# USBasp_SMD.net
KiCad netlist of a schematic drawn in EAGLE
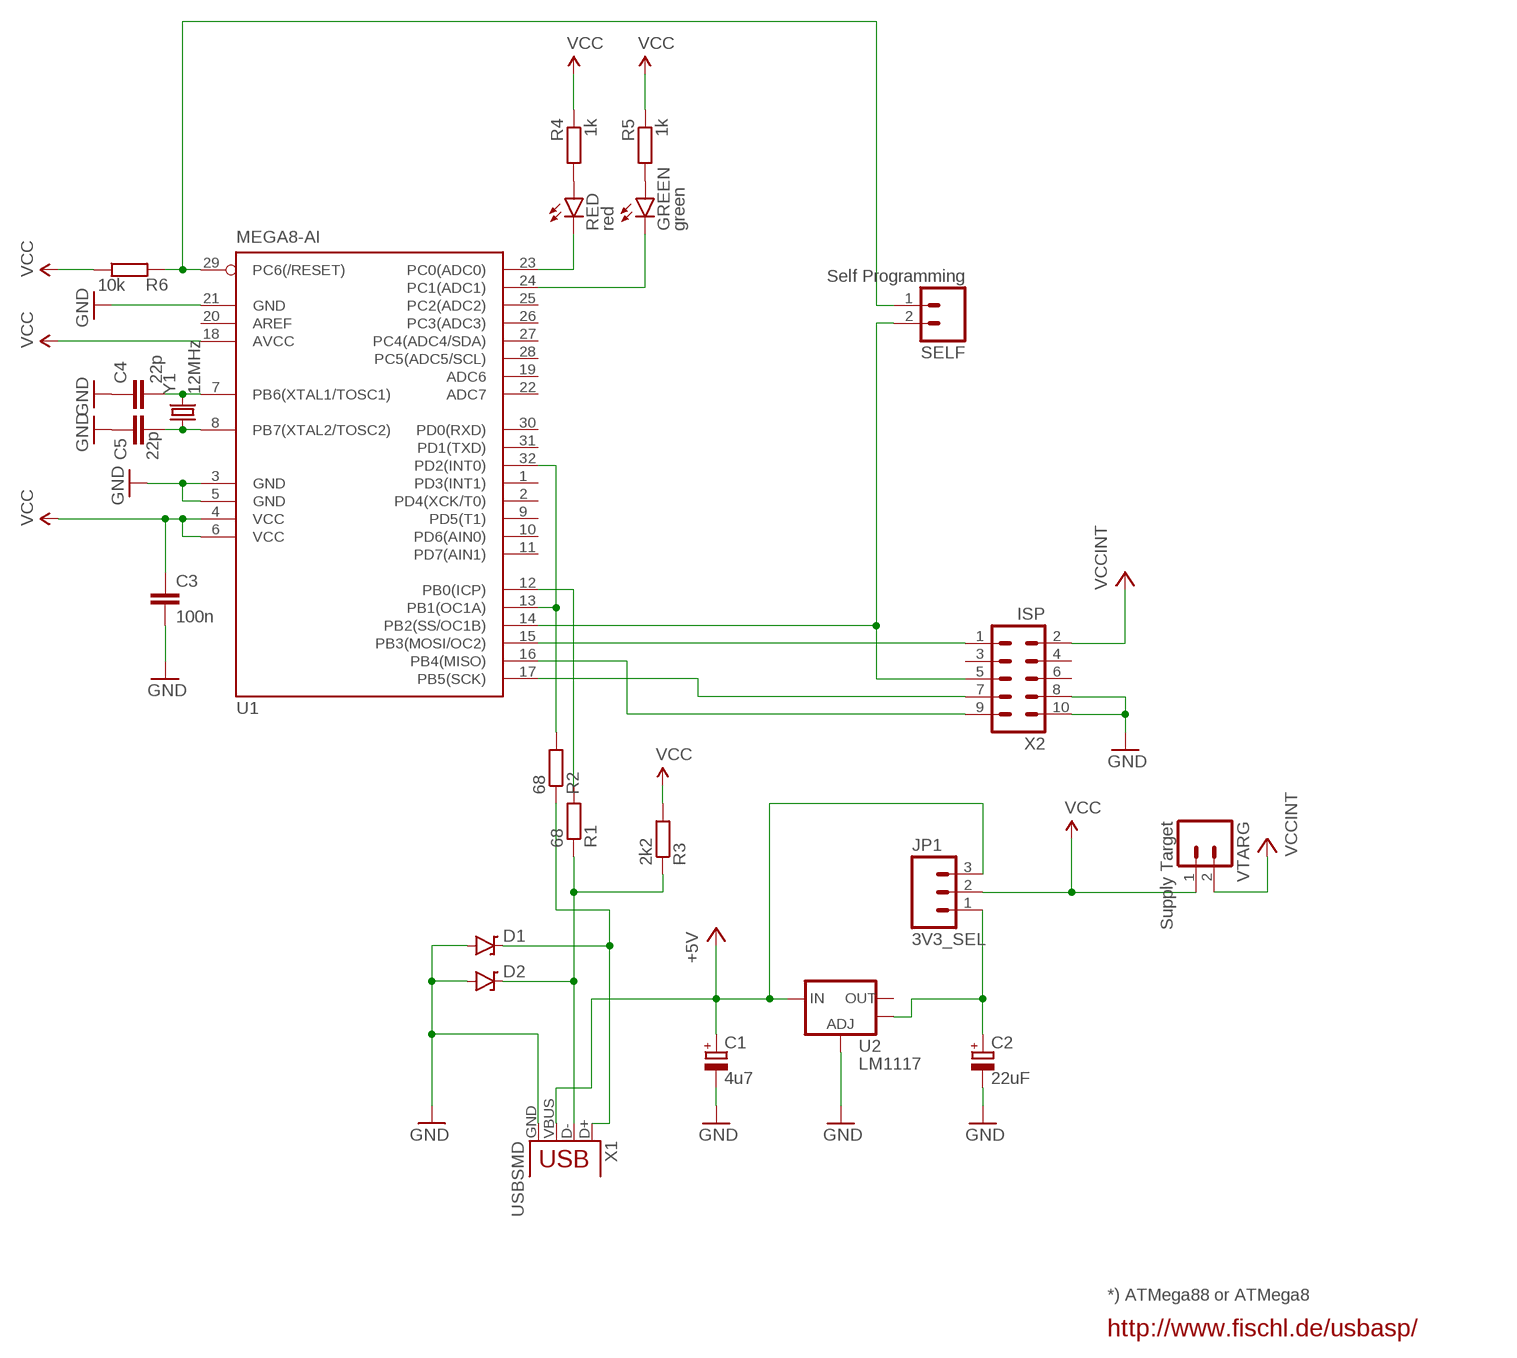
[diagram p0: schematic, sheet 1]

(export (version "E")
  (design (tool "Eeschema 10.0.6"))
  (components
    (comp (ref "C1")
      (value "4u7")
      (footprint "eagle-import:E2,5-5")
      (libsource (lib "eagle-import") (part "CPOL-EUE2.5-5"))
    )
    (comp (ref "C2")
      (value "22uF")
      (footprint "eagle-import:E2,5-5")
      (libsource (lib "eagle-import") (part "CPOL-EUE2.5-5"))
    )
    (comp (ref "C3")
      (value "100n")
      (footprint "eagle-import:C1206")
      (libsource (lib "eagle-import") (part "C-EUC1206"))
    )
    (comp (ref "C4")
      (value "22p")
      (footprint "eagle-import:C1206")
      (libsource (lib "eagle-import") (part "C-EUC1206"))
    )
    (comp (ref "C5")
      (value "22p")
      (footprint "eagle-import:C1206")
      (libsource (lib "eagle-import") (part "C-EUC1206"))
    )
    (comp (ref "D1")
      (value "3V6")
      (footprint "eagle-import:DIODE-ZENER")
      (libsource (lib "eagle-import") (part "DIODE-ZENERPTH"))
    )
    (comp (ref "D2")
      (value "3V6")
      (footprint "eagle-import:DIODE-ZENER")
      (libsource (lib "eagle-import") (part "DIODE-ZENERPTH"))
    )
    (comp (ref "GREEN")
      (value "green")
      (footprint "eagle-import:LED-1206")
      (libsource (lib "eagle-import") (part "LED1206"))
    )
    (comp (ref "JP1")
      (value "3V3_SEL")
      (footprint "eagle-import:1X03")
      (libsource (lib "eagle-import") (part "M03PTH"))
    )
    (comp (ref "R1")
      (value "68")
      (footprint "eagle-import:M1206")
      (libsource (lib "eagle-import") (part "R-EU_M1206"))
    )
    (comp (ref "R2")
      (value "68")
      (footprint "eagle-import:M1206")
      (libsource (lib "eagle-import") (part "R-EU_M1206"))
    )
    (comp (ref "R3")
      (value "2k2")
      (footprint "eagle-import:M1206")
      (libsource (lib "eagle-import") (part "R-EU_M1206"))
    )
    (comp (ref "R4")
      (value "1k")
      (footprint "eagle-import:M1206")
      (libsource (lib "eagle-import") (part "R-EU_M1206"))
    )
    (comp (ref "R5")
      (value "1k")
      (footprint "eagle-import:M1206")
      (libsource (lib "eagle-import") (part "R-EU_M1206"))
    )
    (comp (ref "R6")
      (value "10k")
      (footprint "eagle-import:M1206")
      (libsource (lib "eagle-import") (part "R-EU_M1206"))
    )
    (comp (ref "RED")
      (value "red")
      (footprint "eagle-import:LED-1206")
      (libsource (lib "eagle-import") (part "LED1206"))
    )
    (comp (ref "SELF")
      (value "Self Programming")
      (footprint "eagle-import:1X02")
      (libsource (lib "eagle-import") (part "M02PTH"))
    )
    (comp (ref "U1")
      (value "MEGA8-AI")
      (footprint "eagle-import:TQFP32-08")
      (fields (field (name "MPN") "ATMEGA8-16AU"))
      (libsource (lib "eagle-import") (part "MEGA8-AI"))
    )
    (comp (ref "U2")
      (value "LM1117")
      (footprint "eagle-import:SOT223")
      (libsource (lib "eagle-import") (part "V_REG_LM1117SOT223"))
    )
    (comp (ref "VTARG")
      (value "Supply Target")
      (footprint "eagle-import:1X02")
      (libsource (lib "eagle-import") (part "M02PTH"))
    )
    (comp (ref "X1")
      (value "USBSMD")
      (footprint "eagle-import:USB-MINIB")
      (libsource (lib "eagle-import") (part "USBSMD"))
    )
    (comp (ref "X2")
      (value "ISP")
      (footprint "eagle-import:ML10L")
      (libsource (lib "eagle-import") (part "ML10L"))
    )
    (comp (ref "Y1")
      (value "12MHz")
      (footprint "eagle-import:HC49UP")
      (libsource (lib "eagle-import") (part "CRYSTALSMD"))
    )
  )
  (nets
    (net (code "1") (name "+5V") (class "Default")
      (node (ref "C1") (pin "+") (pinfunction "+_+") (pintype "passive"))
      (node (ref "JP1") (pin "3") (pinfunction "3_3") (pintype "passive"))
      (node (ref "U2") (pin "3") (pinfunction "IN_3") (pintype "input"))
      (node (ref "X1") (pin "VBUS") (pinfunction "VBUS_VBUS") (pintype "bidirectional"))
    )
    (net (code "2") (name "GND") (class "Default")
      (node (ref "C1") (pin "-") (pinfunction "-_-") (pintype "passive"))
      (node (ref "C2") (pin "-") (pinfunction "-_-") (pintype "passive"))
      (node (ref "C3") (pin "2") (pinfunction "2_2") (pintype "passive"))
      (node (ref "C4") (pin "1") (pinfunction "1_1") (pintype "passive"))
      (node (ref "C5") (pin "1") (pinfunction "1_1") (pintype "passive"))
      (node (ref "D1") (pin "P$2") (pinfunction "A_P$2") (pintype "passive"))
      (node (ref "D2") (pin "P$2") (pinfunction "A_P$2") (pintype "passive"))
      (node (ref "U1") (pin "21") (pinfunction "GND_21") (pintype "power_in"))
      (node (ref "U1") (pin "3") (pinfunction "GND_3") (pintype "power_in"))
      (node (ref "U1") (pin "5") (pinfunction "GND_5") (pintype "power_in"))
      (node (ref "U2") (pin "1") (pinfunction "ADJ_1") (pintype "input"))
      (node (ref "X1") (pin "GND") (pinfunction "GND_GND") (pintype "bidirectional"))
      (node (ref "X2") (pin "10") (pinfunction "10_10") (pintype "passive"))
      (node (ref "X2") (pin "8") (pinfunction "8_8") (pintype "passive"))
    )
    (net (code "3") (name "Net-(C2-Pad+)") (class "Default")
      (node (ref "C2") (pin "+") (pinfunction "+_+") (pintype "passive"))
      (node (ref "JP1") (pin "1") (pinfunction "1_1") (pintype "passive"))
      (node (ref "U2") (pin "4") (pinfunction "OUT_4") (pintype "output"))
    )
    (net (code "4") (name "Net-(D1-C)") (class "Default")
      (node (ref "D1") (pin "P$1") (pinfunction "C_P$1") (pintype "passive"))
      (node (ref "R2") (pin "1") (pinfunction "1_1") (pintype "passive"))
      (node (ref "X1") (pin "D+") (pinfunction "D+_D+") (pintype "bidirectional"))
    )
    (net (code "5") (name "Net-(D2-C)") (class "Default")
      (node (ref "D2") (pin "P$1") (pinfunction "C_P$1") (pintype "passive"))
      (node (ref "R1") (pin "1") (pinfunction "1_1") (pintype "passive"))
      (node (ref "R3") (pin "1") (pinfunction "1_1") (pintype "passive"))
      (node (ref "X1") (pin "D-") (pinfunction "D-_D-") (pintype "bidirectional"))
    )
    (net (code "6") (name "Net-(GREEN-PadA)") (class "Default")
      (node (ref "GREEN") (pin "A") (pinfunction "A_A") (pintype "passive"))
      (node (ref "R5") (pin "2") (pinfunction "2_2") (pintype "passive"))
    )
    (net (code "7") (name "Net-(R4-Pad2)") (class "Default")
      (node (ref "R4") (pin "2") (pinfunction "2_2") (pintype "passive"))
      (node (ref "RED") (pin "A") (pinfunction "A_A") (pintype "passive"))
    )
    (net (code "8") (name "Net-(U1-PB0(ICP))") (class "Default")
      (node (ref "R1") (pin "2") (pinfunction "2_2") (pintype "passive"))
      (node (ref "U1") (pin "12") (pinfunction "PB0(ICP)_12") (pintype "bidirectional"))
    )
    (net (code "9") (name "Net-(U1-PB1(OC1A))") (class "Default")
      (node (ref "R2") (pin "2") (pinfunction "2_2") (pintype "passive"))
      (node (ref "U1") (pin "13") (pinfunction "PB1(OC1A)_13") (pintype "bidirectional"))
      (node (ref "U1") (pin "32") (pinfunction "PD2(INT0)_32") (pintype "bidirectional"))
    )
    (net (code "10") (name "Net-(U1-PB2(SS{slash}OC1B))") (class "Default")
      (node (ref "SELF") (pin "2") (pinfunction "2_2") (pintype "passive"))
      (node (ref "U1") (pin "14") (pinfunction "PB2(SS/OC1B)_14") (pintype "bidirectional"))
      (node (ref "X2") (pin "5") (pinfunction "5_5") (pintype "passive"))
    )
    (net (code "11") (name "Net-(U1-PB3(MOSI{slash}OC2))") (class "Default")
      (node (ref "U1") (pin "15") (pinfunction "PB3(MOSI/OC2)_15") (pintype "bidirectional"))
      (node (ref "X2") (pin "1") (pinfunction "1_1") (pintype "passive"))
    )
    (net (code "12") (name "Net-(U1-PB4(MISO))") (class "Default")
      (node (ref "U1") (pin "16") (pinfunction "PB4(MISO)_16") (pintype "bidirectional"))
      (node (ref "X2") (pin "9") (pinfunction "9_9") (pintype "passive"))
    )
    (net (code "13") (name "Net-(U1-PB5(SCK))") (class "Default")
      (node (ref "U1") (pin "17") (pinfunction "PB5(SCK)_17") (pintype "bidirectional"))
      (node (ref "X2") (pin "7") (pinfunction "7_7") (pintype "passive"))
    )
    (net (code "14") (name "Net-(U1-PB6(XTAL1{slash}TOSC1))") (class "Default")
      (node (ref "C4") (pin "2") (pinfunction "2_2") (pintype "passive"))
      (node (ref "U1") (pin "7") (pinfunction "PB6(XTAL1/TOSC1)_7") (pintype "bidirectional"))
      (node (ref "Y1") (pin "2") (pinfunction "2_2") (pintype "passive"))
    )
    (net (code "15") (name "Net-(U1-PB7(XTAL2{slash}TOSC2))") (class "Default")
      (node (ref "C5") (pin "2") (pinfunction "2_2") (pintype "passive"))
      (node (ref "U1") (pin "8") (pinfunction "PB7(XTAL2/TOSC2)_8") (pintype "bidirectional"))
      (node (ref "Y1") (pin "1") (pinfunction "1_1") (pintype "passive"))
    )
    (net (code "16") (name "Net-(U1-PC0(ADC0))") (class "Default")
      (node (ref "RED") (pin "C") (pinfunction "C_C") (pintype "passive"))
      (node (ref "U1") (pin "23") (pinfunction "PC0(ADC0)_23") (pintype "bidirectional"))
    )
    (net (code "17") (name "Net-(U1-PC1(ADC1))") (class "Default")
      (node (ref "GREEN") (pin "C") (pinfunction "C_C") (pintype "passive"))
      (node (ref "U1") (pin "24") (pinfunction "PC1(ADC1)_24") (pintype "bidirectional"))
    )
    (net (code "18") (name "Net-(U1-PC6({slash}RESET))") (class "Default")
      (node (ref "R6") (pin "2") (pinfunction "2_2") (pintype "passive"))
      (node (ref "SELF") (pin "1") (pinfunction "1_1") (pintype "passive"))
      (node (ref "U1") (pin "29") (pinfunction "PC6(/RESET)_29") (pintype "bidirectional"))
    )
    (net (code "19") (name "VCC") (class "Default")
      (node (ref "C3") (pin "1") (pinfunction "1_1") (pintype "passive"))
      (node (ref "JP1") (pin "2") (pinfunction "2_2") (pintype "passive"))
      (node (ref "R3") (pin "2") (pinfunction "2_2") (pintype "passive"))
      (node (ref "R4") (pin "1") (pinfunction "1_1") (pintype "passive"))
      (node (ref "R5") (pin "1") (pinfunction "1_1") (pintype "passive"))
      (node (ref "R6") (pin "1") (pinfunction "1_1") (pintype "passive"))
      (node (ref "U1") (pin "18") (pinfunction "AVCC_18") (pintype "power_in"))
      (node (ref "U1") (pin "4") (pinfunction "VCC_4") (pintype "power_in"))
      (node (ref "U1") (pin "6") (pinfunction "VCC_6") (pintype "power_in"))
      (node (ref "VTARG") (pin "1") (pinfunction "1_1") (pintype "passive"))
    )
    (net (code "20") (name "VCCINT") (class "Default")
      (node (ref "VTARG") (pin "2") (pinfunction "2_2") (pintype "passive"))
      (node (ref "X2") (pin "2") (pinfunction "2_2") (pintype "passive"))
    )
    (net (code "21") (name "unconnected-(U1-ADC6-Pad19)") (class "Default")
      (node (ref "U1") (pin "19") (pinfunction "ADC6_19") (pintype "bidirectional"))
    )
    (net (code "22") (name "unconnected-(U1-ADC7-Pad22)") (class "Default")
      (node (ref "U1") (pin "22") (pinfunction "ADC7_22") (pintype "bidirectional"))
    )
    (net (code "23") (name "unconnected-(U1-AREF-Pad20)") (class "Default")
      (node (ref "U1") (pin "20") (pinfunction "AREF_20") (pintype "passive"))
    )
    (net (code "24") (name "unconnected-(U1-PC2(ADC2)-Pad25)") (class "Default")
      (node (ref "U1") (pin "25") (pinfunction "PC2(ADC2)_25") (pintype "bidirectional"))
    )
    (net (code "25") (name "unconnected-(U1-PC3(ADC3)-Pad26)") (class "Default")
      (node (ref "U1") (pin "26") (pinfunction "PC3(ADC3)_26") (pintype "bidirectional"))
    )
    (net (code "26") (name "unconnected-(U1-PC4(ADC4{slash}SDA)-Pad27)") (class "Default")
      (node (ref "U1") (pin "27") (pinfunction "PC4(ADC4/SDA)_27") (pintype "bidirectional"))
    )
    (net (code "27") (name "unconnected-(U1-PC5(ADC5{slash}SCL)-Pad28)") (class "Default")
      (node (ref "U1") (pin "28") (pinfunction "PC5(ADC5/SCL)_28") (pintype "bidirectional"))
    )
    (net (code "28") (name "unconnected-(U1-PD0(RXD)-Pad30)") (class "Default")
      (node (ref "U1") (pin "30") (pinfunction "PD0(RXD)_30") (pintype "bidirectional"))
    )
    (net (code "29") (name "unconnected-(U1-PD1(TXD)-Pad31)") (class "Default")
      (node (ref "U1") (pin "31") (pinfunction "PD1(TXD)_31") (pintype "bidirectional"))
    )
    (net (code "30") (name "unconnected-(U1-PD3(INT1)-Pad1)") (class "Default")
      (node (ref "U1") (pin "1") (pinfunction "PD3(INT1)_1") (pintype "bidirectional"))
    )
    (net (code "31") (name "unconnected-(U1-PD4(XCK{slash}T0)-Pad2)") (class "Default")
      (node (ref "U1") (pin "2") (pinfunction "PD4(XCK/T0)_2") (pintype "bidirectional"))
    )
    (net (code "32") (name "unconnected-(U1-PD5(T1)-Pad9)") (class "Default")
      (node (ref "U1") (pin "9") (pinfunction "PD5(T1)_9") (pintype "bidirectional"))
    )
    (net (code "33") (name "unconnected-(U1-PD6(AIN0)-Pad10)") (class "Default")
      (node (ref "U1") (pin "10") (pinfunction "PD6(AIN0)_10") (pintype "bidirectional"))
    )
    (net (code "34") (name "unconnected-(U1-PD7(AIN1)-Pad11)") (class "Default")
      (node (ref "U1") (pin "11") (pinfunction "PD7(AIN1)_11") (pintype "bidirectional"))
    )
    (net (code "35") (name "unconnected-(U2-OUT-Pad2)") (class "Default")
      (node (ref "U2") (pin "2") (pinfunction "OUT_2") (pintype "output"))
    )
    (net (code "36") (name "unconnected-(X2-Pad3)") (class "Default")
      (node (ref "X2") (pin "3") (pinfunction "3_3") (pintype "passive"))
    )
    (net (code "37") (name "unconnected-(X2-Pad4)") (class "Default")
      (node (ref "X2") (pin "4") (pinfunction "4_4") (pintype "passive"))
    )
    (net (code "38") (name "unconnected-(X2-Pad6)") (class "Default")
      (node (ref "X2") (pin "6") (pinfunction "6_6") (pintype "passive"))
    )
  )
)
